# piezo-driver_v0_4-R001.net
KiCad netlist of a schematic drawn in EAGLE
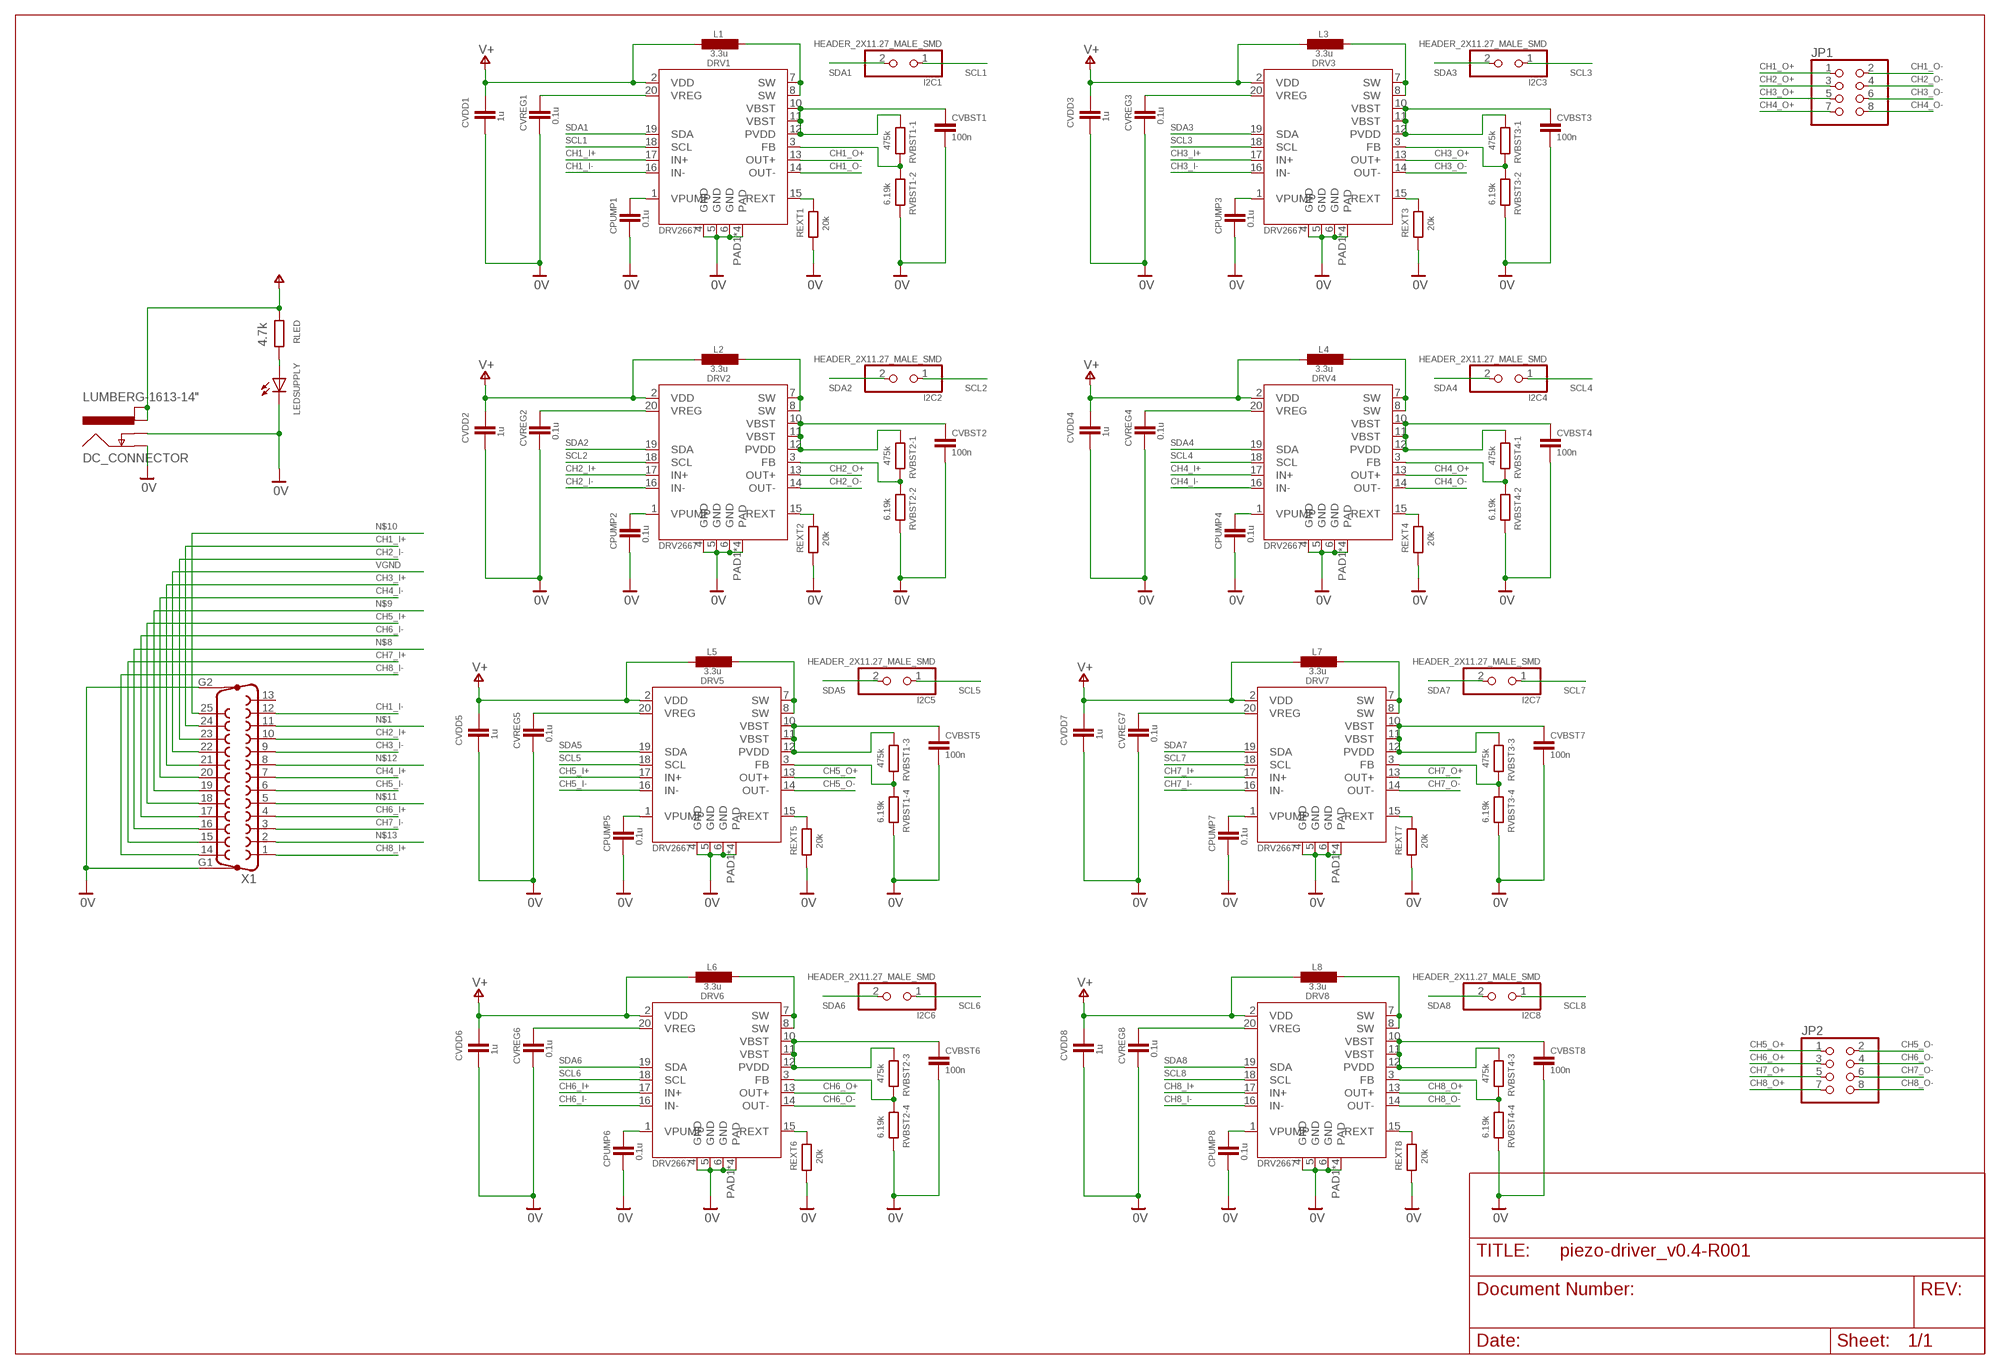
[diagram p0: schematic, sheet 1]

(export (version "E")
  (design (tool "Eeschema 10.0.6"))
  (components
    (comp (ref "CPUMP1")
      (value "0.1u")
      (footprint "eagle-import:C0805")
      (libsource (lib "eagle-import") (part "C-EUC0805"))
    )
    (comp (ref "CPUMP2")
      (value "0.1u")
      (footprint "eagle-import:C0805")
      (libsource (lib "eagle-import") (part "C-EUC0805"))
    )
    (comp (ref "CPUMP3")
      (value "0.1u")
      (footprint "eagle-import:C0805")
      (libsource (lib "eagle-import") (part "C-EUC0805"))
    )
    (comp (ref "CPUMP4")
      (value "0.1u")
      (footprint "eagle-import:C0805")
      (libsource (lib "eagle-import") (part "C-EUC0805"))
    )
    (comp (ref "CPUMP5")
      (value "0.1u")
      (footprint "eagle-import:C0805")
      (libsource (lib "eagle-import") (part "C-EUC0805"))
    )
    (comp (ref "CPUMP6")
      (value "0.1u")
      (footprint "eagle-import:C0805")
      (libsource (lib "eagle-import") (part "C-EUC0805"))
    )
    (comp (ref "CPUMP7")
      (value "0.1u")
      (footprint "eagle-import:C0805")
      (libsource (lib "eagle-import") (part "C-EUC0805"))
    )
    (comp (ref "CPUMP8")
      (value "0.1u")
      (footprint "eagle-import:C0805")
      (libsource (lib "eagle-import") (part "C-EUC0805"))
    )
    (comp (ref "CVBST1")
      (value "100n")
      (footprint "eagle-import:C0805")
      (libsource (lib "eagle-import") (part "C-EUC0805"))
    )
    (comp (ref "CVBST2")
      (value "100n")
      (footprint "eagle-import:C0805")
      (libsource (lib "eagle-import") (part "C-EUC0805"))
    )
    (comp (ref "CVBST3")
      (value "100n")
      (footprint "eagle-import:C0805")
      (libsource (lib "eagle-import") (part "C-EUC0805"))
    )
    (comp (ref "CVBST4")
      (value "100n")
      (footprint "eagle-import:C0805")
      (libsource (lib "eagle-import") (part "C-EUC0805"))
    )
    (comp (ref "CVBST5")
      (value "100n")
      (footprint "eagle-import:C0805")
      (libsource (lib "eagle-import") (part "C-EUC0805"))
    )
    (comp (ref "CVBST6")
      (value "100n")
      (footprint "eagle-import:C0805")
      (libsource (lib "eagle-import") (part "C-EUC0805"))
    )
    (comp (ref "CVBST7")
      (value "100n")
      (footprint "eagle-import:C0805")
      (libsource (lib "eagle-import") (part "C-EUC0805"))
    )
    (comp (ref "CVBST8")
      (value "100n")
      (footprint "eagle-import:C0805")
      (libsource (lib "eagle-import") (part "C-EUC0805"))
    )
    (comp (ref "CVDD1")
      (value "1u")
      (footprint "eagle-import:C0805")
      (libsource (lib "eagle-import") (part "C-EUC0805"))
    )
    (comp (ref "CVDD2")
      (value "1u")
      (footprint "eagle-import:C0805")
      (libsource (lib "eagle-import") (part "C-EUC0805"))
    )
    (comp (ref "CVDD3")
      (value "1u")
      (footprint "eagle-import:C0805")
      (libsource (lib "eagle-import") (part "C-EUC0805"))
    )
    (comp (ref "CVDD4")
      (value "1u")
      (footprint "eagle-import:C0805")
      (libsource (lib "eagle-import") (part "C-EUC0805"))
    )
    (comp (ref "CVDD5")
      (value "1u")
      (footprint "eagle-import:C0805")
      (libsource (lib "eagle-import") (part "C-EUC0805"))
    )
    (comp (ref "CVDD6")
      (value "1u")
      (footprint "eagle-import:C0805")
      (libsource (lib "eagle-import") (part "C-EUC0805"))
    )
    (comp (ref "CVDD7")
      (value "1u")
      (footprint "eagle-import:C0805")
      (libsource (lib "eagle-import") (part "C-EUC0805"))
    )
    (comp (ref "CVDD8")
      (value "1u")
      (footprint "eagle-import:C0805")
      (libsource (lib "eagle-import") (part "C-EUC0805"))
    )
    (comp (ref "CVREG1")
      (value "0.1u")
      (footprint "eagle-import:C0805")
      (libsource (lib "eagle-import") (part "C-EUC0805"))
    )
    (comp (ref "CVREG2")
      (value "0.1u")
      (footprint "eagle-import:C0805")
      (libsource (lib "eagle-import") (part "C-EUC0805"))
    )
    (comp (ref "CVREG3")
      (value "0.1u")
      (footprint "eagle-import:C0805")
      (libsource (lib "eagle-import") (part "C-EUC0805"))
    )
    (comp (ref "CVREG4")
      (value "0.1u")
      (footprint "eagle-import:C0805")
      (libsource (lib "eagle-import") (part "C-EUC0805"))
    )
    (comp (ref "CVREG5")
      (value "0.1u")
      (footprint "eagle-import:C0805")
      (libsource (lib "eagle-import") (part "C-EUC0805"))
    )
    (comp (ref "CVREG6")
      (value "0.1u")
      (footprint "eagle-import:C0805")
      (libsource (lib "eagle-import") (part "C-EUC0805"))
    )
    (comp (ref "CVREG7")
      (value "0.1u")
      (footprint "eagle-import:C0805")
      (libsource (lib "eagle-import") (part "C-EUC0805"))
    )
    (comp (ref "CVREG8")
      (value "0.1u")
      (footprint "eagle-import:C0805")
      (libsource (lib "eagle-import") (part "C-EUC0805"))
    )
    (comp (ref "DC_CONNECTOR")
      (value "LUMBERG-1613-14\"")
      (footprint "eagle-import:LUMBERG-1613_14")
      (libsource (lib "eagle-import") (part "LUMBERG-1613-14{dblquote}"))
    )
    (comp (ref "DRV1")
      (value "DRV2667QFN")
      (footprint "eagle-import:QFN400X400")
      (libsource (lib "eagle-import") (part "DRV2667QFN"))
    )
    (comp (ref "DRV2")
      (value "DRV2667QFN")
      (footprint "eagle-import:QFN400X400")
      (libsource (lib "eagle-import") (part "DRV2667QFN"))
    )
    (comp (ref "DRV3")
      (value "DRV2667QFN")
      (footprint "eagle-import:QFN400X400")
      (libsource (lib "eagle-import") (part "DRV2667QFN"))
    )
    (comp (ref "DRV4")
      (value "DRV2667QFN")
      (footprint "eagle-import:QFN400X400")
      (libsource (lib "eagle-import") (part "DRV2667QFN"))
    )
    (comp (ref "DRV5")
      (value "DRV2667QFN")
      (footprint "eagle-import:QFN400X400")
      (libsource (lib "eagle-import") (part "DRV2667QFN"))
    )
    (comp (ref "DRV6")
      (value "DRV2667QFN")
      (footprint "eagle-import:QFN400X400")
      (libsource (lib "eagle-import") (part "DRV2667QFN"))
    )
    (comp (ref "DRV7")
      (value "DRV2667QFN")
      (footprint "eagle-import:QFN400X400")
      (libsource (lib "eagle-import") (part "DRV2667QFN"))
    )
    (comp (ref "DRV8")
      (value "DRV2667QFN")
      (footprint "eagle-import:QFN400X400")
      (libsource (lib "eagle-import") (part "DRV2667QFN"))
    )
    (comp (ref "I2C1")
      (value "HEADER_2X11.27_MALE_SMD")
      (footprint "eagle-import:2X01_1.27_SMD")
      (libsource (lib "eagle-import") (part "HEADER_2X11.27_MALE_SMD"))
    )
    (comp (ref "I2C2")
      (value "HEADER_2X11.27_MALE_SMD")
      (footprint "eagle-import:2X01_1.27_SMD")
      (libsource (lib "eagle-import") (part "HEADER_2X11.27_MALE_SMD"))
    )
    (comp (ref "I2C3")
      (value "HEADER_2X11.27_MALE_SMD")
      (footprint "eagle-import:2X01_1.27_SMD")
      (libsource (lib "eagle-import") (part "HEADER_2X11.27_MALE_SMD"))
    )
    (comp (ref "I2C4")
      (value "HEADER_2X11.27_MALE_SMD")
      (footprint "eagle-import:2X01_1.27_SMD")
      (libsource (lib "eagle-import") (part "HEADER_2X11.27_MALE_SMD"))
    )
    (comp (ref "I2C5")
      (value "HEADER_2X11.27_MALE_SMD")
      (footprint "eagle-import:2X01_1.27_SMD")
      (libsource (lib "eagle-import") (part "HEADER_2X11.27_MALE_SMD"))
    )
    (comp (ref "I2C6")
      (value "HEADER_2X11.27_MALE_SMD")
      (footprint "eagle-import:2X01_1.27_SMD")
      (libsource (lib "eagle-import") (part "HEADER_2X11.27_MALE_SMD"))
    )
    (comp (ref "I2C7")
      (value "HEADER_2X11.27_MALE_SMD")
      (footprint "eagle-import:2X01_1.27_SMD")
      (libsource (lib "eagle-import") (part "HEADER_2X11.27_MALE_SMD"))
    )
    (comp (ref "I2C8")
      (value "HEADER_2X11.27_MALE_SMD")
      (footprint "eagle-import:2X01_1.27_SMD")
      (libsource (lib "eagle-import") (part "HEADER_2X11.27_MALE_SMD"))
    )
    (comp (ref "JP1")
      (value "PINHD-2X4/90")
      (footprint "eagle-import:2X04_90")
      (libsource (lib "eagle-import") (part "PINHD-2X4/90"))
    )
    (comp (ref "JP2")
      (value "PINHD-2X4/90")
      (footprint "eagle-import:2X04_90")
      (libsource (lib "eagle-import") (part "PINHD-2X4/90"))
    )
    (comp (ref "L1")
      (value "3.3u")
      (footprint "eagle-import:L3225M")
      (libsource (lib "eagle-import") (part "L-EUL3225M"))
    )
    (comp (ref "L2")
      (value "3.3u")
      (footprint "eagle-import:L3225M")
      (libsource (lib "eagle-import") (part "L-EUL3225M"))
    )
    (comp (ref "L3")
      (value "3.3u")
      (footprint "eagle-import:L3225M")
      (libsource (lib "eagle-import") (part "L-EUL3225M"))
    )
    (comp (ref "L4")
      (value "3.3u")
      (footprint "eagle-import:L3225M")
      (libsource (lib "eagle-import") (part "L-EUL3225M"))
    )
    (comp (ref "L5")
      (value "3.3u")
      (footprint "eagle-import:L3225M")
      (libsource (lib "eagle-import") (part "L-EUL3225M"))
    )
    (comp (ref "L6")
      (value "3.3u")
      (footprint "eagle-import:L3225M")
      (libsource (lib "eagle-import") (part "L-EUL3225M"))
    )
    (comp (ref "L7")
      (value "3.3u")
      (footprint "eagle-import:L3225M")
      (libsource (lib "eagle-import") (part "L-EUL3225M"))
    )
    (comp (ref "L8")
      (value "3.3u")
      (footprint "eagle-import:L3225M")
      (libsource (lib "eagle-import") (part "L-EUL3225M"))
    )
    (comp (ref "LEDSUPPLY")
      (value "LED0603")
      (footprint "eagle-import:LED-0603")
      (libsource (lib "eagle-import") (part "LED0603"))
    )
    (comp (ref "REXT1")
      (value "20k")
      (footprint "eagle-import:R0805")
      (libsource (lib "eagle-import") (part "R-EU_R0805"))
    )
    (comp (ref "REXT2")
      (value "20k")
      (footprint "eagle-import:R0805")
      (libsource (lib "eagle-import") (part "R-EU_R0805"))
    )
    (comp (ref "REXT3")
      (value "20k")
      (footprint "eagle-import:R0805")
      (libsource (lib "eagle-import") (part "R-EU_R0805"))
    )
    (comp (ref "REXT4")
      (value "20k")
      (footprint "eagle-import:R0805")
      (libsource (lib "eagle-import") (part "R-EU_R0805"))
    )
    (comp (ref "REXT5")
      (value "20k")
      (footprint "eagle-import:R0805")
      (libsource (lib "eagle-import") (part "R-EU_R0805"))
    )
    (comp (ref "REXT6")
      (value "20k")
      (footprint "eagle-import:R0805")
      (libsource (lib "eagle-import") (part "R-EU_R0805"))
    )
    (comp (ref "REXT7")
      (value "20k")
      (footprint "eagle-import:R0805")
      (libsource (lib "eagle-import") (part "R-EU_R0805"))
    )
    (comp (ref "REXT8")
      (value "20k")
      (footprint "eagle-import:R0805")
      (libsource (lib "eagle-import") (part "R-EU_R0805"))
    )
    (comp (ref "RLED")
      (value "4.7k")
      (footprint "eagle-import:R0805")
      (libsource (lib "eagle-import") (part "rcl_R-EU_R0805"))
    )
    (comp (ref "RVBST1-1")
      (value "475k")
      (footprint "eagle-import:R0805")
      (libsource (lib "eagle-import") (part "R-EU_R0805"))
    )
    (comp (ref "RVBST1-2")
      (value "6.19k")
      (footprint "eagle-import:R0805")
      (libsource (lib "eagle-import") (part "R-EU_R0805"))
    )
    (comp (ref "RVBST1-3")
      (value "475k")
      (footprint "eagle-import:R0805")
      (libsource (lib "eagle-import") (part "R-EU_R0805"))
    )
    (comp (ref "RVBST1-4")
      (value "6.19k")
      (footprint "eagle-import:R0805")
      (libsource (lib "eagle-import") (part "R-EU_R0805"))
    )
    (comp (ref "RVBST2-1")
      (value "475k")
      (footprint "eagle-import:R0805")
      (libsource (lib "eagle-import") (part "R-EU_R0805"))
    )
    (comp (ref "RVBST2-2")
      (value "6.19k")
      (footprint "eagle-import:R0805")
      (libsource (lib "eagle-import") (part "R-EU_R0805"))
    )
    (comp (ref "RVBST2-3")
      (value "475k")
      (footprint "eagle-import:R0805")
      (libsource (lib "eagle-import") (part "R-EU_R0805"))
    )
    (comp (ref "RVBST2-4")
      (value "6.19k")
      (footprint "eagle-import:R0805")
      (libsource (lib "eagle-import") (part "R-EU_R0805"))
    )
    (comp (ref "RVBST3-1")
      (value "475k")
      (footprint "eagle-import:R0805")
      (libsource (lib "eagle-import") (part "R-EU_R0805"))
    )
    (comp (ref "RVBST3-2")
      (value "6.19k")
      (footprint "eagle-import:R0805")
      (libsource (lib "eagle-import") (part "R-EU_R0805"))
    )
    (comp (ref "RVBST3-3")
      (value "475k")
      (footprint "eagle-import:R0805")
      (libsource (lib "eagle-import") (part "R-EU_R0805"))
    )
    (comp (ref "RVBST3-4")
      (value "6.19k")
      (footprint "eagle-import:R0805")
      (libsource (lib "eagle-import") (part "R-EU_R0805"))
    )
    (comp (ref "RVBST4-1")
      (value "475k")
      (footprint "eagle-import:R0805")
      (libsource (lib "eagle-import") (part "R-EU_R0805"))
    )
    (comp (ref "RVBST4-2")
      (value "6.19k")
      (footprint "eagle-import:R0805")
      (libsource (lib "eagle-import") (part "R-EU_R0805"))
    )
    (comp (ref "RVBST4-3")
      (value "475k")
      (footprint "eagle-import:R0805")
      (libsource (lib "eagle-import") (part "R-EU_R0805"))
    )
    (comp (ref "RVBST4-4")
      (value "6.19k")
      (footprint "eagle-import:R0805")
      (libsource (lib "eagle-import") (part "R-EU_R0805"))
    )
    (comp (ref "X1")
      (value "F25HP")
      (footprint "eagle-import:F25HP")
      (libsource (lib "eagle-import") (part "F25HP"))
    )
  )
  (nets
    (net (code "1") (name "/CH1_I+") (class "Default")
      (node (ref "DRV1") (pin "17") (pinfunction "IN+_17") (pintype "bidirectional"))
      (node (ref "X1") (pin "24") (pinfunction "24_24") (pintype "passive"))
    )
    (net (code "2") (name "/CH1_I-") (class "Default")
      (node (ref "DRV1") (pin "16") (pinfunction "IN-_16") (pintype "bidirectional"))
      (node (ref "X1") (pin "12") (pinfunction "12_12") (pintype "passive"))
    )
    (net (code "3") (name "/CH1_O+") (class "Default")
      (node (ref "DRV1") (pin "13") (pinfunction "OUT+_13") (pintype "bidirectional"))
      (node (ref "JP1") (pin "1") (pinfunction "1_1") (pintype "passive"))
    )
    (net (code "4") (name "/CH1_O-") (class "Default")
      (node (ref "DRV1") (pin "14") (pinfunction "OUT-_14") (pintype "bidirectional"))
      (node (ref "JP1") (pin "2") (pinfunction "2_2") (pintype "passive"))
    )
    (net (code "5") (name "/CH2_I+") (class "Default")
      (node (ref "DRV2") (pin "17") (pinfunction "IN+_17") (pintype "bidirectional"))
      (node (ref "X1") (pin "10") (pinfunction "10_10") (pintype "passive"))
    )
    (net (code "6") (name "/CH2_I-") (class "Default")
      (node (ref "DRV2") (pin "16") (pinfunction "IN-_16") (pintype "bidirectional"))
      (node (ref "X1") (pin "23") (pinfunction "23_23") (pintype "passive"))
    )
    (net (code "7") (name "/CH2_O+") (class "Default")
      (node (ref "DRV2") (pin "13") (pinfunction "OUT+_13") (pintype "bidirectional"))
      (node (ref "JP1") (pin "3") (pinfunction "3_3") (pintype "passive"))
    )
    (net (code "8") (name "/CH2_O-") (class "Default")
      (node (ref "DRV2") (pin "14") (pinfunction "OUT-_14") (pintype "bidirectional"))
      (node (ref "JP1") (pin "4") (pinfunction "4_4") (pintype "passive"))
    )
    (net (code "9") (name "/CH3_I+") (class "Default")
      (node (ref "DRV3") (pin "17") (pinfunction "IN+_17") (pintype "bidirectional"))
      (node (ref "X1") (pin "21") (pinfunction "21_21") (pintype "passive"))
    )
    (net (code "10") (name "/CH3_I-") (class "Default")
      (node (ref "DRV3") (pin "16") (pinfunction "IN-_16") (pintype "bidirectional"))
      (node (ref "X1") (pin "9") (pinfunction "9_9") (pintype "passive"))
    )
    (net (code "11") (name "/CH3_O+") (class "Default")
      (node (ref "DRV3") (pin "13") (pinfunction "OUT+_13") (pintype "bidirectional"))
      (node (ref "JP1") (pin "5") (pinfunction "5_5") (pintype "passive"))
    )
    (net (code "12") (name "/CH3_O-") (class "Default")
      (node (ref "DRV3") (pin "14") (pinfunction "OUT-_14") (pintype "bidirectional"))
      (node (ref "JP1") (pin "6") (pinfunction "6_6") (pintype "passive"))
    )
    (net (code "13") (name "/CH4_I+") (class "Default")
      (node (ref "DRV4") (pin "17") (pinfunction "IN+_17") (pintype "bidirectional"))
      (node (ref "X1") (pin "7") (pinfunction "7_7") (pintype "passive"))
    )
    (net (code "14") (name "/CH4_I-") (class "Default")
      (node (ref "DRV4") (pin "16") (pinfunction "IN-_16") (pintype "bidirectional"))
      (node (ref "X1") (pin "20") (pinfunction "20_20") (pintype "passive"))
    )
    (net (code "15") (name "/CH4_O+") (class "Default")
      (node (ref "DRV4") (pin "13") (pinfunction "OUT+_13") (pintype "bidirectional"))
      (node (ref "JP1") (pin "7") (pinfunction "7_7") (pintype "passive"))
    )
    (net (code "16") (name "/CH4_O-") (class "Default")
      (node (ref "DRV4") (pin "14") (pinfunction "OUT-_14") (pintype "bidirectional"))
      (node (ref "JP1") (pin "8") (pinfunction "8_8") (pintype "passive"))
    )
    (net (code "17") (name "/CH5_I+") (class "Default")
      (node (ref "DRV5") (pin "17") (pinfunction "IN+_17") (pintype "bidirectional"))
      (node (ref "X1") (pin "18") (pinfunction "18_18") (pintype "passive"))
    )
    (net (code "18") (name "/CH5_I-") (class "Default")
      (node (ref "DRV5") (pin "16") (pinfunction "IN-_16") (pintype "bidirectional"))
      (node (ref "X1") (pin "6") (pinfunction "6_6") (pintype "passive"))
    )
    (net (code "19") (name "/CH5_O+") (class "Default")
      (node (ref "DRV5") (pin "13") (pinfunction "OUT+_13") (pintype "bidirectional"))
      (node (ref "JP2") (pin "1") (pinfunction "1_1") (pintype "passive"))
    )
    (net (code "20") (name "/CH5_O-") (class "Default")
      (node (ref "DRV5") (pin "14") (pinfunction "OUT-_14") (pintype "bidirectional"))
      (node (ref "JP2") (pin "2") (pinfunction "2_2") (pintype "passive"))
    )
    (net (code "21") (name "/CH6_I+") (class "Default")
      (node (ref "DRV6") (pin "17") (pinfunction "IN+_17") (pintype "bidirectional"))
      (node (ref "X1") (pin "4") (pinfunction "4_4") (pintype "passive"))
    )
    (net (code "22") (name "/CH6_I-") (class "Default")
      (node (ref "DRV6") (pin "16") (pinfunction "IN-_16") (pintype "bidirectional"))
      (node (ref "X1") (pin "17") (pinfunction "17_17") (pintype "passive"))
    )
    (net (code "23") (name "/CH6_O+") (class "Default")
      (node (ref "DRV6") (pin "13") (pinfunction "OUT+_13") (pintype "bidirectional"))
      (node (ref "JP2") (pin "3") (pinfunction "3_3") (pintype "passive"))
    )
    (net (code "24") (name "/CH6_O-") (class "Default")
      (node (ref "DRV6") (pin "14") (pinfunction "OUT-_14") (pintype "bidirectional"))
      (node (ref "JP2") (pin "4") (pinfunction "4_4") (pintype "passive"))
    )
    (net (code "25") (name "/CH7_I+") (class "Default")
      (node (ref "DRV7") (pin "17") (pinfunction "IN+_17") (pintype "bidirectional"))
      (node (ref "X1") (pin "15") (pinfunction "15_15") (pintype "passive"))
    )
    (net (code "26") (name "/CH7_I-") (class "Default")
      (node (ref "DRV7") (pin "16") (pinfunction "IN-_16") (pintype "bidirectional"))
      (node (ref "X1") (pin "3") (pinfunction "3_3") (pintype "passive"))
    )
    (net (code "27") (name "/CH7_O+") (class "Default")
      (node (ref "DRV7") (pin "13") (pinfunction "OUT+_13") (pintype "bidirectional"))
      (node (ref "JP2") (pin "5") (pinfunction "5_5") (pintype "passive"))
    )
    (net (code "28") (name "/CH7_O-") (class "Default")
      (node (ref "DRV7") (pin "14") (pinfunction "OUT-_14") (pintype "bidirectional"))
      (node (ref "JP2") (pin "6") (pinfunction "6_6") (pintype "passive"))
    )
    (net (code "29") (name "/CH8_I+") (class "Default")
      (node (ref "DRV8") (pin "17") (pinfunction "IN+_17") (pintype "bidirectional"))
      (node (ref "X1") (pin "1") (pinfunction "1_1") (pintype "passive"))
    )
    (net (code "30") (name "/CH8_I-") (class "Default")
      (node (ref "DRV8") (pin "16") (pinfunction "IN-_16") (pintype "bidirectional"))
      (node (ref "X1") (pin "14") (pinfunction "14_14") (pintype "passive"))
    )
    (net (code "31") (name "/CH8_O+") (class "Default")
      (node (ref "DRV8") (pin "13") (pinfunction "OUT+_13") (pintype "bidirectional"))
      (node (ref "JP2") (pin "7") (pinfunction "7_7") (pintype "passive"))
    )
    (net (code "32") (name "/CH8_O-") (class "Default")
      (node (ref "DRV8") (pin "14") (pinfunction "OUT-_14") (pintype "bidirectional"))
      (node (ref "JP2") (pin "8") (pinfunction "8_8") (pintype "passive"))
    )
    (net (code "33") (name "/N$1") (class "Default")
      (node (ref "X1") (pin "11") (pinfunction "11_11") (pintype "passive"))
    )
    (net (code "34") (name "/N$8") (class "Default")
      (node (ref "X1") (pin "16") (pinfunction "16_16") (pintype "passive"))
    )
    (net (code "35") (name "/N$9") (class "Default")
      (node (ref "X1") (pin "19") (pinfunction "19_19") (pintype "passive"))
    )
    (net (code "36") (name "/N$10") (class "Default")
      (node (ref "X1") (pin "25") (pinfunction "25_25") (pintype "passive"))
    )
    (net (code "37") (name "/N$11") (class "Default")
      (node (ref "X1") (pin "5") (pinfunction "5_5") (pintype "passive"))
    )
    (net (code "38") (name "/N$12") (class "Default")
      (node (ref "X1") (pin "8") (pinfunction "8_8") (pintype "passive"))
    )
    (net (code "39") (name "/N$13") (class "Default")
      (node (ref "X1") (pin "2") (pinfunction "2_2") (pintype "passive"))
    )
    (net (code "40") (name "/SCL1") (class "Default")
      (node (ref "DRV1") (pin "18") (pinfunction "SCL_18") (pintype "bidirectional"))
      (node (ref "I2C1") (pin "1") (pinfunction "1_1") (pintype "passive"))
    )
    (net (code "41") (name "/SCL2") (class "Default")
      (node (ref "DRV2") (pin "18") (pinfunction "SCL_18") (pintype "bidirectional"))
      (node (ref "I2C2") (pin "1") (pinfunction "1_1") (pintype "passive"))
    )
    (net (code "42") (name "/SCL3") (class "Default")
      (node (ref "DRV3") (pin "18") (pinfunction "SCL_18") (pintype "bidirectional"))
      (node (ref "I2C3") (pin "1") (pinfunction "1_1") (pintype "passive"))
    )
    (net (code "43") (name "/SCL4") (class "Default")
      (node (ref "DRV4") (pin "18") (pinfunction "SCL_18") (pintype "bidirectional"))
      (node (ref "I2C4") (pin "1") (pinfunction "1_1") (pintype "passive"))
    )
    (net (code "44") (name "/SCL5") (class "Default")
      (node (ref "DRV5") (pin "18") (pinfunction "SCL_18") (pintype "bidirectional"))
      (node (ref "I2C5") (pin "1") (pinfunction "1_1") (pintype "passive"))
    )
    (net (code "45") (name "/SCL6") (class "Default")
      (node (ref "DRV6") (pin "18") (pinfunction "SCL_18") (pintype "bidirectional"))
      (node (ref "I2C6") (pin "1") (pinfunction "1_1") (pintype "passive"))
    )
    (net (code "46") (name "/SCL7") (class "Default")
      (node (ref "DRV7") (pin "18") (pinfunction "SCL_18") (pintype "bidirectional"))
      (node (ref "I2C7") (pin "1") (pinfunction "1_1") (pintype "passive"))
    )
    (net (code "47") (name "/SCL8") (class "Default")
      (node (ref "DRV8") (pin "18") (pinfunction "SCL_18") (pintype "bidirectional"))
      (node (ref "I2C8") (pin "1") (pinfunction "1_1") (pintype "passive"))
    )
    (net (code "48") (name "/SDA1") (class "Default")
      (node (ref "DRV1") (pin "19") (pinfunction "SDA_19") (pintype "bidirectional"))
      (node (ref "I2C1") (pin "2") (pinfunction "2_2") (pintype "passive"))
    )
    (net (code "49") (name "/SDA2") (class "Default")
      (node (ref "DRV2") (pin "19") (pinfunction "SDA_19") (pintype "bidirectional"))
      (node (ref "I2C2") (pin "2") (pinfunction "2_2") (pintype "passive"))
    )
    (net (code "50") (name "/SDA3") (class "Default")
      (node (ref "DRV3") (pin "19") (pinfunction "SDA_19") (pintype "bidirectional"))
      (node (ref "I2C3") (pin "2") (pinfunction "2_2") (pintype "passive"))
    )
    (net (code "51") (name "/SDA4") (class "Default")
      (node (ref "DRV4") (pin "19") (pinfunction "SDA_19") (pintype "bidirectional"))
      (node (ref "I2C4") (pin "2") (pinfunction "2_2") (pintype "passive"))
    )
    (net (code "52") (name "/SDA5") (class "Default")
      (node (ref "DRV5") (pin "19") (pinfunction "SDA_19") (pintype "bidirectional"))
      (node (ref "I2C5") (pin "2") (pinfunction "2_2") (pintype "passive"))
    )
    (net (code "53") (name "/SDA6") (class "Default")
      (node (ref "DRV6") (pin "19") (pinfunction "SDA_19") (pintype "bidirectional"))
      (node (ref "I2C6") (pin "2") (pinfunction "2_2") (pintype "passive"))
    )
    (net (code "54") (name "/SDA7") (class "Default")
      (node (ref "DRV7") (pin "19") (pinfunction "SDA_19") (pintype "bidirectional"))
      (node (ref "I2C7") (pin "2") (pinfunction "2_2") (pintype "passive"))
    )
    (net (code "55") (name "/SDA8") (class "Default")
      (node (ref "DRV8") (pin "19") (pinfunction "SDA_19") (pintype "bidirectional"))
      (node (ref "I2C8") (pin "2") (pinfunction "2_2") (pintype "passive"))
    )
    (net (code "56") (name "/VGND") (class "Default")
      (node (ref "X1") (pin "22") (pinfunction "22_22") (pintype "passive"))
    )
    (net (code "57") (name "0V") (class "Default")
      (node (ref "CPUMP1") (pin "2") (pinfunction "2_2") (pintype "passive"))
      (node (ref "CPUMP2") (pin "2") (pinfunction "2_2") (pintype "passive"))
      (node (ref "CPUMP3") (pin "2") (pinfunction "2_2") (pintype "passive"))
      (node (ref "CPUMP4") (pin "2") (pinfunction "2_2") (pintype "passive"))
      (node (ref "CPUMP5") (pin "2") (pinfunction "2_2") (pintype "passive"))
      (node (ref "CPUMP6") (pin "2") (pinfunction "2_2") (pintype "passive"))
      (node (ref "CPUMP7") (pin "2") (pinfunction "2_2") (pintype "passive"))
      (node (ref "CPUMP8") (pin "2") (pinfunction "2_2") (pintype "passive"))
      (node (ref "CVBST1") (pin "2") (pinfunction "2_2") (pintype "passive"))
      (node (ref "CVBST2") (pin "2") (pinfunction "2_2") (pintype "passive"))
      (node (ref "CVBST3") (pin "2") (pinfunction "2_2") (pintype "passive"))
      (node (ref "CVBST4") (pin "2") (pinfunction "2_2") (pintype "passive"))
      (node (ref "CVBST5") (pin "2") (pinfunction "2_2") (pintype "passive"))
      (node (ref "CVBST6") (pin "2") (pinfunction "2_2") (pintype "passive"))
      (node (ref "CVBST7") (pin "2") (pinfunction "2_2") (pintype "passive"))
      (node (ref "CVBST8") (pin "2") (pinfunction "2_2") (pintype "passive"))
      (node (ref "CVDD1") (pin "2") (pinfunction "2_2") (pintype "passive"))
      (node (ref "CVDD2") (pin "2") (pinfunction "2_2") (pintype "passive"))
      (node (ref "CVDD3") (pin "2") (pinfunction "2_2") (pintype "passive"))
      (node (ref "CVDD4") (pin "2") (pinfunction "2_2") (pintype "passive"))
      (node (ref "CVDD5") (pin "2") (pinfunction "2_2") (pintype "passive"))
      (node (ref "CVDD6") (pin "2") (pinfunction "2_2") (pintype "passive"))
      (node (ref "CVDD7") (pin "2") (pinfunction "2_2") (pintype "passive"))
      (node (ref "CVDD8") (pin "2") (pinfunction "2_2") (pintype "passive"))
      (node (ref "CVREG1") (pin "2") (pinfunction "2_2") (pintype "passive"))
      (node (ref "CVREG2") (pin "2") (pinfunction "2_2") (pintype "passive"))
      (node (ref "CVREG3") (pin "2") (pinfunction "2_2") (pintype "passive"))
      (node (ref "CVREG4") (pin "2") (pinfunction "2_2") (pintype "passive"))
      (node (ref "CVREG5") (pin "2") (pinfunction "2_2") (pintype "passive"))
      (node (ref "CVREG6") (pin "2") (pinfunction "2_2") (pintype "passive"))
      (node (ref "CVREG7") (pin "2") (pinfunction "2_2") (pintype "passive"))
      (node (ref "CVREG8") (pin "2") (pinfunction "2_2") (pintype "passive"))
      (node (ref "DC_CONNECTOR") (pin "1") (pinfunction "GND_1") (pintype "power_in"))
      (node (ref "DC_CONNECTOR") (pin "2") (pinfunction "GND_INS_2") (pintype "power_in"))
      (node (ref "DRV1") (pin "4") (pinfunction "GND_4") (pintype "bidirectional"))
      (node (ref "DRV1") (pin "5") (pinfunction "GND_5") (pintype "bidirectional"))
      (node (ref "DRV1") (pin "6") (pinfunction "GND_6") (pintype "bidirectional"))
      (node (ref "DRV1") (pin "PAD1") (pinfunction "PAD_PAD1") (pintype "bidirectional"))
      (node (ref "DRV1") (pin "PAD2") (pinfunction "PAD_PAD2") (pintype "bidirectional"))
      (node (ref "DRV1") (pin "PAD3") (pinfunction "PAD_PAD3") (pintype "bidirectional"))
      (node (ref "DRV1") (pin "PAD4") (pinfunction "PAD_PAD4") (pintype "bidirectional"))
      (node (ref "DRV2") (pin "4") (pinfunction "GND_4") (pintype "bidirectional"))
      (node (ref "DRV2") (pin "5") (pinfunction "GND_5") (pintype "bidirectional"))
      (node (ref "DRV2") (pin "6") (pinfunction "GND_6") (pintype "bidirectional"))
      (node (ref "DRV2") (pin "PAD1") (pinfunction "PAD_PAD1") (pintype "bidirectional"))
      (node (ref "DRV2") (pin "PAD2") (pinfunction "PAD_PAD2") (pintype "bidirectional"))
      (node (ref "DRV2") (pin "PAD3") (pinfunction "PAD_PAD3") (pintype "bidirectional"))
      (node (ref "DRV2") (pin "PAD4") (pinfunction "PAD_PAD4") (pintype "bidirectional"))
      (node (ref "DRV3") (pin "4") (pinfunction "GND_4") (pintype "bidirectional"))
      (node (ref "DRV3") (pin "5") (pinfunction "GND_5") (pintype "bidirectional"))
      (node (ref "DRV3") (pin "6") (pinfunction "GND_6") (pintype "bidirectional"))
      (node (ref "DRV3") (pin "PAD1") (pinfunction "PAD_PAD1") (pintype "bidirectional"))
      (node (ref "DRV3") (pin "PAD2") (pinfunction "PAD_PAD2") (pintype "bidirectional"))
      (node (ref "DRV3") (pin "PAD3") (pinfunction "PAD_PAD3") (pintype "bidirectional"))
      (node (ref "DRV3") (pin "PAD4") (pinfunction "PAD_PAD4") (pintype "bidirectional"))
      (node (ref "DRV4") (pin "4") (pinfunction "GND_4") (pintype "bidirectional"))
      (node (ref "DRV4") (pin "5") (pinfunction "GND_5") (pintype "bidirectional"))
      (node (ref "DRV4") (pin "6") (pinfunction "GND_6") (pintype "bidirectional"))
      (node (ref "DRV4") (pin "PAD1") (pinfunction "PAD_PAD1") (pintype "bidirectional"))
      (node (ref "DRV4") (pin "PAD2") (pinfunction "PAD_PAD2") (pintype "bidirectional"))
      (node (ref "DRV4") (pin "PAD3") (pinfunction "PAD_PAD3") (pintype "bidirectional"))
      (node (ref "DRV4") (pin "PAD4") (pinfunction "PAD_PAD4") (pintype "bidirectional"))
      (node (ref "DRV5") (pin "4") (pinfunction "GND_4") (pintype "bidirectional"))
      (node (ref "DRV5") (pin "5") (pinfunction "GND_5") (pintype "bidirectional"))
      (node (ref "DRV5") (pin "6") (pinfunction "GND_6") (pintype "bidirectional"))
      (node (ref "DRV5") (pin "PAD1") (pinfunction "PAD_PAD1") (pintype "bidirectional"))
      (node (ref "DRV5") (pin "PAD2") (pinfunction "PAD_PAD2") (pintype "bidirectional"))
      (node (ref "DRV5") (pin "PAD3") (pinfunction "PAD_PAD3") (pintype "bidirectional"))
      (node (ref "DRV5") (pin "PAD4") (pinfunction "PAD_PAD4") (pintype "bidirectional"))
      (node (ref "DRV6") (pin "4") (pinfunction "GND_4") (pintype "bidirectional"))
      (node (ref "DRV6") (pin "5") (pinfunction "GND_5") (pintype "bidirectional"))
      (node (ref "DRV6") (pin "6") (pinfunction "GND_6") (pintype "bidirectional"))
      (node (ref "DRV6") (pin "PAD1") (pinfunction "PAD_PAD1") (pintype "bidirectional"))
      (node (ref "DRV6") (pin "PAD2") (pinfunction "PAD_PAD2") (pintype "bidirectional"))
      (node (ref "DRV6") (pin "PAD3") (pinfunction "PAD_PAD3") (pintype "bidirectional"))
      (node (ref "DRV6") (pin "PAD4") (pinfunction "PAD_PAD4") (pintype "bidirectional"))
      (node (ref "DRV7") (pin "4") (pinfunction "GND_4") (pintype "bidirectional"))
      (node (ref "DRV7") (pin "5") (pinfunction "GND_5") (pintype "bidirectional"))
      (node (ref "DRV7") (pin "6") (pinfunction "GND_6") (pintype "bidirectional"))
      (node (ref "DRV7") (pin "PAD1") (pinfunction "PAD_PAD1") (pintype "bidirectional"))
      (node (ref "DRV7") (pin "PAD2") (pinfunction "PAD_PAD2") (pintype "bidirectional"))
      (node (ref "DRV7") (pin "PAD3") (pinfunction "PAD_PAD3") (pintype "bidirectional"))
      (node (ref "DRV7") (pin "PAD4") (pinfunction "PAD_PAD4") (pintype "bidirectional"))
      (node (ref "DRV8") (pin "4") (pinfunction "GND_4") (pintype "bidirectional"))
      (node (ref "DRV8") (pin "5") (pinfunction "GND_5") (pintype "bidirectional"))
      (node (ref "DRV8") (pin "6") (pinfunction "GND_6") (pintype "bidirectional"))
      (node (ref "DRV8") (pin "PAD1") (pinfunction "PAD_PAD1") (pintype "bidirectional"))
      (node (ref "DRV8") (pin "PAD2") (pinfunction "PAD_PAD2") (pintype "bidirectional"))
      (node (ref "DRV8") (pin "PAD3") (pinfunction "PAD_PAD3") (pintype "bidirectional"))
      (node (ref "DRV8") (pin "PAD4") (pinfunction "PAD_PAD4") (pintype "bidirectional"))
      (node (ref "LEDSUPPLY") (pin "C") (pinfunction "C_C") (pintype "passive"))
      (node (ref "REXT1") (pin "1") (pinfunction "1_1") (pintype "passive"))
      (node (ref "REXT2") (pin "1") (pinfunction "1_1") (pintype "passive"))
      (node (ref "REXT3") (pin "1") (pinfunction "1_1") (pintype "passive"))
      (node (ref "REXT4") (pin "1") (pinfunction "1_1") (pintype "passive"))
      (node (ref "REXT5") (pin "1") (pinfunction "1_1") (pintype "passive"))
      (node (ref "REXT6") (pin "1") (pinfunction "1_1") (pintype "passive"))
      (node (ref "REXT7") (pin "1") (pinfunction "1_1") (pintype "passive"))
      (node (ref "REXT8") (pin "1") (pinfunction "1_1") (pintype "passive"))
      (node (ref "RVBST1-2") (pin "1") (pinfunction "1_1") (pintype "passive"))
      (node (ref "RVBST1-4") (pin "1") (pinfunction "1_1") (pintype "passive"))
      (node (ref "RVBST2-2") (pin "1") (pinfunction "1_1") (pintype "passive"))
      (node (ref "RVBST2-4") (pin "1") (pinfunction "1_1") (pintype "passive"))
      (node (ref "RVBST3-2") (pin "1") (pinfunction "1_1") (pintype "passive"))
      (node (ref "RVBST3-4") (pin "1") (pinfunction "1_1") (pintype "passive"))
      (node (ref "RVBST4-2") (pin "1") (pinfunction "1_1") (pintype "passive"))
      (node (ref "RVBST4-4") (pin "1") (pinfunction "1_1") (pintype "passive"))
      (node (ref "X1") (pin "G1") (pinfunction "G1_G1") (pintype "passive"))
      (node (ref "X1") (pin "G2") (pinfunction "G2_G2") (pintype "passive"))
    )
    (net (code "58") (name "Net-(DRV1-FB)") (class "Default")
      (node (ref "DRV1") (pin "3") (pinfunction "FB_3") (pintype "bidirectional"))
      (node (ref "RVBST1-1") (pin "1") (pinfunction "1_1") (pintype "passive"))
      (node (ref "RVBST1-2") (pin "2") (pinfunction "2_2") (pintype "passive"))
    )
    (net (code "59") (name "Net-(DRV1-PVDD)") (class "Default")
      (node (ref "CVBST1") (pin "1") (pinfunction "1_1") (pintype "passive"))
      (node (ref "DRV1") (pin "10") (pinfunction "VBST_10") (pintype "bidirectional"))
      (node (ref "DRV1") (pin "11") (pinfunction "VBST_11") (pintype "bidirectional"))
      (node (ref "DRV1") (pin "12") (pinfunction "PVDD_12") (pintype "bidirectional"))
      (node (ref "RVBST1-1") (pin "2") (pinfunction "2_2") (pintype "passive"))
    )
    (net (code "60") (name "Net-(DRV1-REXT)") (class "Default")
      (node (ref "DRV1") (pin "15") (pinfunction "REXT_15") (pintype "bidirectional"))
      (node (ref "REXT1") (pin "2") (pinfunction "2_2") (pintype "passive"))
    )
    (net (code "61") (name "Net-(DRV1-SW-Pad7)") (class "Default")
      (node (ref "DRV1") (pin "7") (pinfunction "SW_7") (pintype "bidirectional"))
      (node (ref "DRV1") (pin "8") (pinfunction "SW_8") (pintype "bidirectional"))
      (node (ref "L1") (pin "1") (pinfunction "1_1") (pintype "passive"))
    )
    (net (code "62") (name "Net-(DRV1-VPUMP)") (class "Default")
      (node (ref "CPUMP1") (pin "1") (pinfunction "1_1") (pintype "passive"))
      (node (ref "DRV1") (pin "1") (pinfunction "VPUMP_1") (pintype "bidirectional"))
    )
    (net (code "63") (name "Net-(DRV1-VREG)") (class "Default")
      (node (ref "CVREG1") (pin "1") (pinfunction "1_1") (pintype "passive"))
      (node (ref "DRV1") (pin "20") (pinfunction "VREG_20") (pintype "bidirectional"))
    )
    (net (code "64") (name "Net-(DRV2-FB)") (class "Default")
      (node (ref "DRV2") (pin "3") (pinfunction "FB_3") (pintype "bidirectional"))
      (node (ref "RVBST2-1") (pin "1") (pinfunction "1_1") (pintype "passive"))
      (node (ref "RVBST2-2") (pin "2") (pinfunction "2_2") (pintype "passive"))
    )
    (net (code "65") (name "Net-(DRV2-PVDD)") (class "Default")
      (node (ref "CVBST2") (pin "1") (pinfunction "1_1") (pintype "passive"))
      (node (ref "DRV2") (pin "10") (pinfunction "VBST_10") (pintype "bidirectional"))
      (node (ref "DRV2") (pin "11") (pinfunction "VBST_11") (pintype "bidirectional"))
      (node (ref "DRV2") (pin "12") (pinfunction "PVDD_12") (pintype "bidirectional"))
      (node (ref "RVBST2-1") (pin "2") (pinfunction "2_2") (pintype "passive"))
    )
    (net (code "66") (name "Net-(DRV2-REXT)") (class "Default")
      (node (ref "DRV2") (pin "15") (pinfunction "REXT_15") (pintype "bidirectional"))
      (node (ref "REXT2") (pin "2") (pinfunction "2_2") (pintype "passive"))
    )
    (net (code "67") (name "Net-(DRV2-SW-Pad7)") (class "Default")
      (node (ref "DRV2") (pin "7") (pinfunction "SW_7") (pintype "bidirectional"))
      (node (ref "DRV2") (pin "8") (pinfunction "SW_8") (pintype "bidirectional"))
      (node (ref "L2") (pin "1") (pinfunction "1_1") (pintype "passive"))
    )
    (net (code "68") (name "Net-(DRV2-VPUMP)") (class "Default")
      (node (ref "CPUMP2") (pin "1") (pinfunction "1_1") (pintype "passive"))
      (node (ref "DRV2") (pin "1") (pinfunction "VPUMP_1") (pintype "bidirectional"))
    )
    (net (code "69") (name "Net-(DRV2-VREG)") (class "Default")
      (node (ref "CVREG2") (pin "1") (pinfunction "1_1") (pintype "passive"))
      (node (ref "DRV2") (pin "20") (pinfunction "VREG_20") (pintype "bidirectional"))
    )
    (net (code "70") (name "Net-(DRV3-FB)") (class "Default")
      (node (ref "DRV3") (pin "3") (pinfunction "FB_3") (pintype "bidirectional"))
      (node (ref "RVBST3-1") (pin "1") (pinfunction "1_1") (pintype "passive"))
      (node (ref "RVBST3-2") (pin "2") (pinfunction "2_2") (pintype "passive"))
    )
    (net (code "71") (name "Net-(DRV3-PVDD)") (class "Default")
      (node (ref "CVBST3") (pin "1") (pinfunction "1_1") (pintype "passive"))
      (node (ref "DRV3") (pin "10") (pinfunction "VBST_10") (pintype "bidirectional"))
      (node (ref "DRV3") (pin "11") (pinfunction "VBST_11") (pintype "bidirectional"))
      (node (ref "DRV3") (pin "12") (pinfunction "PVDD_12") (pintype "bidirectional"))
      (node (ref "RVBST3-1") (pin "2") (pinfunction "2_2") (pintype "passive"))
    )
    (net (code "72") (name "Net-(DRV3-REXT)") (class "Default")
      (node (ref "DRV3") (pin "15") (pinfunction "REXT_15") (pintype "bidirectional"))
      (node (ref "REXT3") (pin "2") (pinfunction "2_2") (pintype "passive"))
    )
    (net (code "73") (name "Net-(DRV3-SW-Pad7)") (class "Default")
      (node (ref "DRV3") (pin "7") (pinfunction "SW_7") (pintype "bidirectional"))
      (node (ref "DRV3") (pin "8") (pinfunction "SW_8") (pintype "bidirectional"))
      (node (ref "L3") (pin "1") (pinfunction "1_1") (pintype "passive"))
    )
    (net (code "74") (name "Net-(DRV3-VPUMP)") (class "Default")
      (node (ref "CPUMP3") (pin "1") (pinfunction "1_1") (pintype "passive"))
      (node (ref "DRV3") (pin "1") (pinfunction "VPUMP_1") (pintype "bidirectional"))
    )
    (net (code "75") (name "Net-(DRV3-VREG)") (class "Default")
      (node (ref "CVREG3") (pin "1") (pinfunction "1_1") (pintype "passive"))
      (node (ref "DRV3") (pin "20") (pinfunction "VREG_20") (pintype "bidirectional"))
    )
    (net (code "76") (name "Net-(DRV4-FB)") (class "Default")
      (node (ref "DRV4") (pin "3") (pinfunction "FB_3") (pintype "bidirectional"))
      (node (ref "RVBST4-1") (pin "1") (pinfunction "1_1") (pintype "passive"))
      (node (ref "RVBST4-2") (pin "2") (pinfunction "2_2") (pintype "passive"))
    )
    (net (code "77") (name "Net-(DRV4-PVDD)") (class "Default")
      (node (ref "CVBST4") (pin "1") (pinfunction "1_1") (pintype "passive"))
      (node (ref "DRV4") (pin "10") (pinfunction "VBST_10") (pintype "bidirectional"))
      (node (ref "DRV4") (pin "11") (pinfunction "VBST_11") (pintype "bidirectional"))
      (node (ref "DRV4") (pin "12") (pinfunction "PVDD_12") (pintype "bidirectional"))
      (node (ref "RVBST4-1") (pin "2") (pinfunction "2_2") (pintype "passive"))
    )
    (net (code "78") (name "Net-(DRV4-REXT)") (class "Default")
      (node (ref "DRV4") (pin "15") (pinfunction "REXT_15") (pintype "bidirectional"))
      (node (ref "REXT4") (pin "2") (pinfunction "2_2") (pintype "passive"))
    )
    (net (code "79") (name "Net-(DRV4-SW-Pad7)") (class "Default")
      (node (ref "DRV4") (pin "7") (pinfunction "SW_7") (pintype "bidirectional"))
      (node (ref "DRV4") (pin "8") (pinfunction "SW_8") (pintype "bidirectional"))
      (node (ref "L4") (pin "1") (pinfunction "1_1") (pintype "passive"))
    )
    (net (code "80") (name "Net-(DRV4-VPUMP)") (class "Default")
      (node (ref "CPUMP4") (pin "1") (pinfunction "1_1") (pintype "passive"))
      (node (ref "DRV4") (pin "1") (pinfunction "VPUMP_1") (pintype "bidirectional"))
    )
    (net (code "81") (name "Net-(DRV4-VREG)") (class "Default")
      (node (ref "CVREG4") (pin "1") (pinfunction "1_1") (pintype "passive"))
      (node (ref "DRV4") (pin "20") (pinfunction "VREG_20") (pintype "bidirectional"))
    )
    (net (code "82") (name "Net-(DRV5-FB)") (class "Default")
      (node (ref "DRV5") (pin "3") (pinfunction "FB_3") (pintype "bidirectional"))
      (node (ref "RVBST1-3") (pin "1") (pinfunction "1_1") (pintype "passive"))
      (node (ref "RVBST1-4") (pin "2") (pinfunction "2_2") (pintype "passive"))
    )
    (net (code "83") (name "Net-(DRV5-PVDD)") (class "Default")
      (node (ref "CVBST5") (pin "1") (pinfunction "1_1") (pintype "passive"))
      (node (ref "DRV5") (pin "10") (pinfunction "VBST_10") (pintype "bidirectional"))
      (node (ref "DRV5") (pin "11") (pinfunction "VBST_11") (pintype "bidirectional"))
      (node (ref "DRV5") (pin "12") (pinfunction "PVDD_12") (pintype "bidirectional"))
      (node (ref "RVBST1-3") (pin "2") (pinfunction "2_2") (pintype "passive"))
    )
    (net (code "84") (name "Net-(DRV5-REXT)") (class "Default")
      (node (ref "DRV5") (pin "15") (pinfunction "REXT_15") (pintype "bidirectional"))
      (node (ref "REXT5") (pin "2") (pinfunction "2_2") (pintype "passive"))
    )
    (net (code "85") (name "Net-(DRV5-SW-Pad7)") (class "Default")
      (node (ref "DRV5") (pin "7") (pinfunction "SW_7") (pintype "bidirectional"))
      (node (ref "DRV5") (pin "8") (pinfunction "SW_8") (pintype "bidirectional"))
      (node (ref "L5") (pin "1") (pinfunction "1_1") (pintype "passive"))
    )
    (net (code "86") (name "Net-(DRV5-VPUMP)") (class "Default")
      (node (ref "CPUMP5") (pin "1") (pinfunction "1_1") (pintype "passive"))
      (node (ref "DRV5") (pin "1") (pinfunction "VPUMP_1") (pintype "bidirectional"))
    )
    (net (code "87") (name "Net-(DRV5-VREG)") (class "Default")
      (node (ref "CVREG5") (pin "1") (pinfunction "1_1") (pintype "passive"))
      (node (ref "DRV5") (pin "20") (pinfunction "VREG_20") (pintype "bidirectional"))
    )
    (net (code "88") (name "Net-(DRV6-FB)") (class "Default")
      (node (ref "DRV6") (pin "3") (pinfunction "FB_3") (pintype "bidirectional"))
      (node (ref "RVBST2-3") (pin "1") (pinfunction "1_1") (pintype "passive"))
      (node (ref "RVBST2-4") (pin "2") (pinfunction "2_2") (pintype "passive"))
    )
    (net (code "89") (name "Net-(DRV6-PVDD)") (class "Default")
      (node (ref "CVBST6") (pin "1") (pinfunction "1_1") (pintype "passive"))
      (node (ref "DRV6") (pin "10") (pinfunction "VBST_10") (pintype "bidirectional"))
      (node (ref "DRV6") (pin "11") (pinfunction "VBST_11") (pintype "bidirectional"))
      (node (ref "DRV6") (pin "12") (pinfunction "PVDD_12") (pintype "bidirectional"))
      (node (ref "RVBST2-3") (pin "2") (pinfunction "2_2") (pintype "passive"))
    )
    (net (code "90") (name "Net-(DRV6-REXT)") (class "Default")
      (node (ref "DRV6") (pin "15") (pinfunction "REXT_15") (pintype "bidirectional"))
      (node (ref "REXT6") (pin "2") (pinfunction "2_2") (pintype "passive"))
    )
    (net (code "91") (name "Net-(DRV6-SW-Pad7)") (class "Default")
      (node (ref "DRV6") (pin "7") (pinfunction "SW_7") (pintype "bidirectional"))
      (node (ref "DRV6") (pin "8") (pinfunction "SW_8") (pintype "bidirectional"))
      (node (ref "L6") (pin "1") (pinfunction "1_1") (pintype "passive"))
    )
    (net (code "92") (name "Net-(DRV6-VPUMP)") (class "Default")
      (node (ref "CPUMP6") (pin "1") (pinfunction "1_1") (pintype "passive"))
      (node (ref "DRV6") (pin "1") (pinfunction "VPUMP_1") (pintype "bidirectional"))
    )
    (net (code "93") (name "Net-(DRV6-VREG)") (class "Default")
      (node (ref "CVREG6") (pin "1") (pinfunction "1_1") (pintype "passive"))
      (node (ref "DRV6") (pin "20") (pinfunction "VREG_20") (pintype "bidirectional"))
    )
    (net (code "94") (name "Net-(DRV7-FB)") (class "Default")
      (node (ref "DRV7") (pin "3") (pinfunction "FB_3") (pintype "bidirectional"))
      (node (ref "RVBST3-3") (pin "1") (pinfunction "1_1") (pintype "passive"))
      (node (ref "RVBST3-4") (pin "2") (pinfunction "2_2") (pintype "passive"))
    )
    (net (code "95") (name "Net-(DRV7-PVDD)") (class "Default")
      (node (ref "CVBST7") (pin "1") (pinfunction "1_1") (pintype "passive"))
      (node (ref "DRV7") (pin "10") (pinfunction "VBST_10") (pintype "bidirectional"))
      (node (ref "DRV7") (pin "11") (pinfunction "VBST_11") (pintype "bidirectional"))
      (node (ref "DRV7") (pin "12") (pinfunction "PVDD_12") (pintype "bidirectional"))
      (node (ref "RVBST3-3") (pin "2") (pinfunction "2_2") (pintype "passive"))
    )
    (net (code "96") (name "Net-(DRV7-REXT)") (class "Default")
      (node (ref "DRV7") (pin "15") (pinfunction "REXT_15") (pintype "bidirectional"))
      (node (ref "REXT7") (pin "2") (pinfunction "2_2") (pintype "passive"))
    )
    (net (code "97") (name "Net-(DRV7-SW-Pad7)") (class "Default")
      (node (ref "DRV7") (pin "7") (pinfunction "SW_7") (pintype "bidirectional"))
      (node (ref "DRV7") (pin "8") (pinfunction "SW_8") (pintype "bidirectional"))
      (node (ref "L7") (pin "1") (pinfunction "1_1") (pintype "passive"))
    )
    (net (code "98") (name "Net-(DRV7-VPUMP)") (class "Default")
      (node (ref "CPUMP7") (pin "1") (pinfunction "1_1") (pintype "passive"))
      (node (ref "DRV7") (pin "1") (pinfunction "VPUMP_1") (pintype "bidirectional"))
    )
    (net (code "99") (name "Net-(DRV7-VREG)") (class "Default")
      (node (ref "CVREG7") (pin "1") (pinfunction "1_1") (pintype "passive"))
      (node (ref "DRV7") (pin "20") (pinfunction "VREG_20") (pintype "bidirectional"))
    )
    (net (code "100") (name "Net-(DRV8-FB)") (class "Default")
      (node (ref "DRV8") (pin "3") (pinfunction "FB_3") (pintype "bidirectional"))
      (node (ref "RVBST4-3") (pin "1") (pinfunction "1_1") (pintype "passive"))
      (node (ref "RVBST4-4") (pin "2") (pinfunction "2_2") (pintype "passive"))
    )
    (net (code "101") (name "Net-(DRV8-PVDD)") (class "Default")
      (node (ref "CVBST8") (pin "1") (pinfunction "1_1") (pintype "passive"))
      (node (ref "DRV8") (pin "10") (pinfunction "VBST_10") (pintype "bidirectional"))
      (node (ref "DRV8") (pin "11") (pinfunction "VBST_11") (pintype "bidirectional"))
      (node (ref "DRV8") (pin "12") (pinfunction "PVDD_12") (pintype "bidirectional"))
      (node (ref "RVBST4-3") (pin "2") (pinfunction "2_2") (pintype "passive"))
    )
    (net (code "102") (name "Net-(DRV8-REXT)") (class "Default")
      (node (ref "DRV8") (pin "15") (pinfunction "REXT_15") (pintype "bidirectional"))
      (node (ref "REXT8") (pin "2") (pinfunction "2_2") (pintype "passive"))
    )
    (net (code "103") (name "Net-(DRV8-SW-Pad7)") (class "Default")
      (node (ref "DRV8") (pin "7") (pinfunction "SW_7") (pintype "bidirectional"))
      (node (ref "DRV8") (pin "8") (pinfunction "SW_8") (pintype "bidirectional"))
      (node (ref "L8") (pin "1") (pinfunction "1_1") (pintype "passive"))
    )
    (net (code "104") (name "Net-(DRV8-VPUMP)") (class "Default")
      (node (ref "CPUMP8") (pin "1") (pinfunction "1_1") (pintype "passive"))
      (node (ref "DRV8") (pin "1") (pinfunction "VPUMP_1") (pintype "bidirectional"))
    )
    (net (code "105") (name "Net-(DRV8-VREG)") (class "Default")
      (node (ref "CVREG8") (pin "1") (pinfunction "1_1") (pintype "passive"))
      (node (ref "DRV8") (pin "20") (pinfunction "VREG_20") (pintype "bidirectional"))
    )
    (net (code "106") (name "Net-(LEDSUPPLY-PadA)") (class "Default")
      (node (ref "LEDSUPPLY") (pin "A") (pinfunction "A_A") (pintype "passive"))
      (node (ref "RLED") (pin "1") (pinfunction "1_1") (pintype "passive"))
    )
    (net (code "107") (name "V+") (class "Default")
      (node (ref "CVDD1") (pin "1") (pinfunction "1_1") (pintype "passive"))
      (node (ref "CVDD2") (pin "1") (pinfunction "1_1") (pintype "passive"))
      (node (ref "CVDD3") (pin "1") (pinfunction "1_1") (pintype "passive"))
      (node (ref "CVDD4") (pin "1") (pinfunction "1_1") (pintype "passive"))
      (node (ref "CVDD5") (pin "1") (pinfunction "1_1") (pintype "passive"))
      (node (ref "CVDD6") (pin "1") (pinfunction "1_1") (pintype "passive"))
      (node (ref "CVDD7") (pin "1") (pinfunction "1_1") (pintype "passive"))
      (node (ref "CVDD8") (pin "1") (pinfunction "1_1") (pintype "passive"))
      (node (ref "DC_CONNECTOR") (pin "3") (pinfunction "PWR_1_3") (pintype "power_in"))
      (node (ref "DC_CONNECTOR") (pin "4") (pinfunction "PWR_2_4") (pintype "power_in"))
      (node (ref "DRV1") (pin "2") (pinfunction "VDD_2") (pintype "bidirectional"))
      (node (ref "DRV2") (pin "2") (pinfunction "VDD_2") (pintype "bidirectional"))
      (node (ref "DRV3") (pin "2") (pinfunction "VDD_2") (pintype "bidirectional"))
      (node (ref "DRV4") (pin "2") (pinfunction "VDD_2") (pintype "bidirectional"))
      (node (ref "DRV5") (pin "2") (pinfunction "VDD_2") (pintype "bidirectional"))
      (node (ref "DRV6") (pin "2") (pinfunction "VDD_2") (pintype "bidirectional"))
      (node (ref "DRV7") (pin "2") (pinfunction "VDD_2") (pintype "bidirectional"))
      (node (ref "DRV8") (pin "2") (pinfunction "VDD_2") (pintype "bidirectional"))
      (node (ref "L1") (pin "2") (pinfunction "2_2") (pintype "passive"))
      (node (ref "L2") (pin "2") (pinfunction "2_2") (pintype "passive"))
      (node (ref "L3") (pin "2") (pinfunction "2_2") (pintype "passive"))
      (node (ref "L4") (pin "2") (pinfunction "2_2") (pintype "passive"))
      (node (ref "L5") (pin "2") (pinfunction "2_2") (pintype "passive"))
      (node (ref "L6") (pin "2") (pinfunction "2_2") (pintype "passive"))
      (node (ref "L7") (pin "2") (pinfunction "2_2") (pintype "passive"))
      (node (ref "L8") (pin "2") (pinfunction "2_2") (pintype "passive"))
      (node (ref "RLED") (pin "2") (pinfunction "2_2") (pintype "passive"))
    )
    (net (code "108") (name "unconnected-(X1-Pad13)") (class "Default")
      (node (ref "X1") (pin "13") (pinfunction "13_13") (pintype "passive"))
    )
  )
)
